# w076o.net
KiCad netlist of a schematic drawn in EAGLE
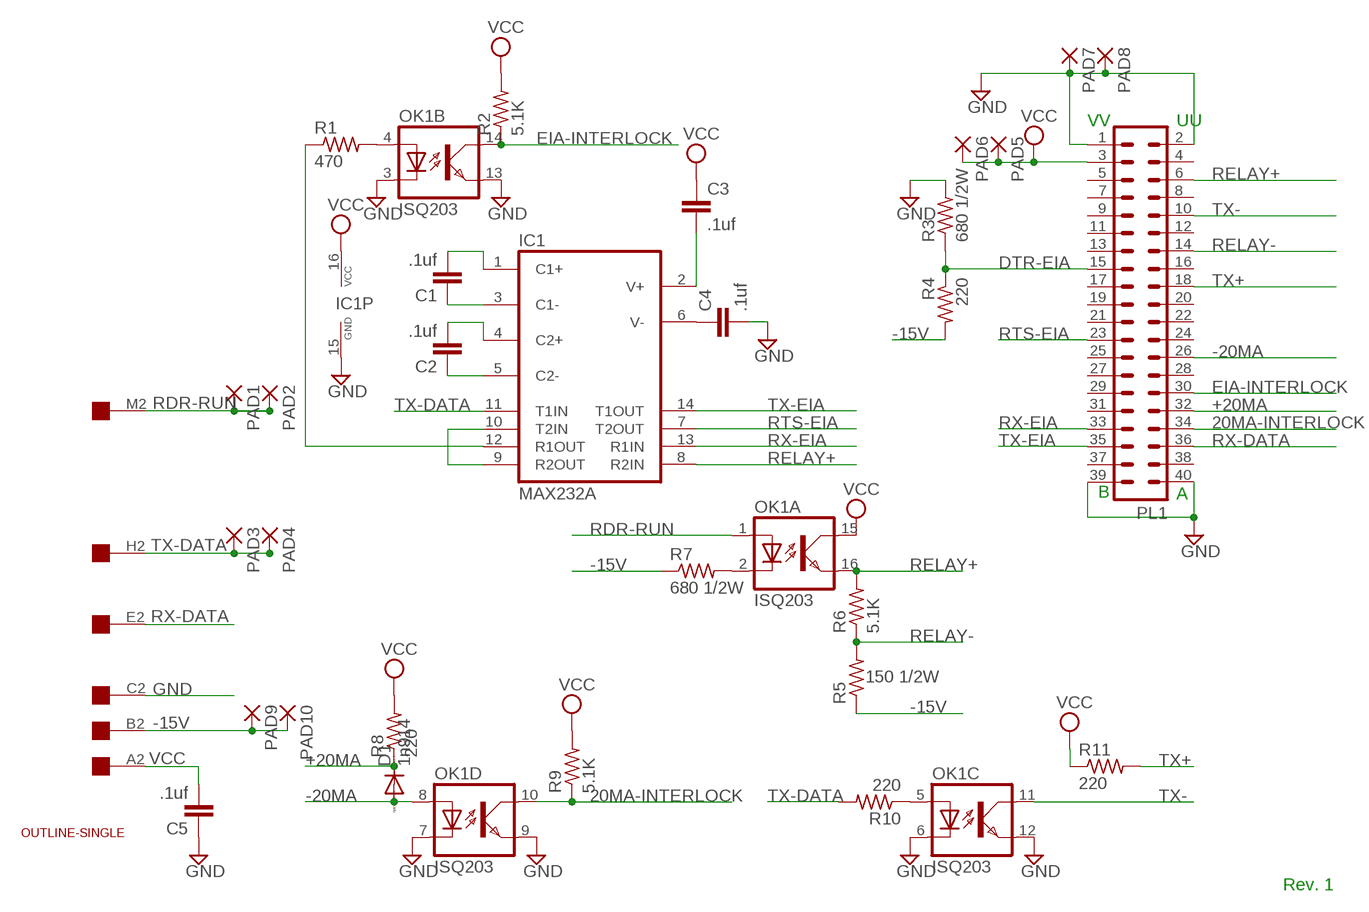
[diagram p0: schematic, sheet 1]

(export (version "E")
  (design (tool "Eeschema 10.0.6"))
  (components
    (comp (ref "C1")
      (value ".1uf")
      (footprint "eagle-import:C050-025X075")
      (libsource (lib "eagle-import") (part "C-EU050-025X075"))
    )
    (comp (ref "C2")
      (value ".1uf")
      (footprint "eagle-import:C050-025X075")
      (libsource (lib "eagle-import") (part "C-EU050-025X075"))
    )
    (comp (ref "C3")
      (value ".1uf")
      (footprint "eagle-import:C050-025X075")
      (libsource (lib "eagle-import") (part "C-EU050-025X075"))
    )
    (comp (ref "C4")
      (value ".1uf")
      (footprint "eagle-import:C050-025X075")
      (libsource (lib "eagle-import") (part "C-EU050-025X075"))
    )
    (comp (ref "C5")
      (value ".1uf")
      (footprint "eagle-import:C050-025X075")
      (libsource (lib "eagle-import") (part "C-EU050-025X075"))
    )
    (comp (ref "D1")
      (value "1n914")
      (footprint "eagle-import:DO41-10")
      (libsource (lib "eagle-import") (part "1N4004"))
    )
    (comp (ref "IC1")
      (value "MAX232A")
      (footprint "eagle-import:DIL16")
      (fields (field (name "MF") "MAXIM") (field (name "MPN") "MAX232ACPE+"))
      (libsource (lib "eagle-import") (part "MAX232"))
    )
    (comp (ref "OK1")
      (value "ISQ203")
      (footprint "eagle-import:DIL16")
      (fields (field (name "MF") "VISHAY/TELEFUNKEN") (field (name "MPN") "ILQ1"))
      (libsource (lib "eagle-import") (part "ILQ1"))
    )
    (comp (ref "PAD1")
      (value "1,6/0,8")
      (footprint "eagle-import:1,6_0,8")
      (libsource (lib "eagle-import") (part "1,6/0,8"))
    )
    (comp (ref "PAD2")
      (value "1,6/0,8")
      (footprint "eagle-import:1,6_0,8")
      (libsource (lib "eagle-import") (part "1,6/0,8"))
    )
    (comp (ref "PAD3")
      (value "1,6/0,8")
      (footprint "eagle-import:1,6_0,8")
      (libsource (lib "eagle-import") (part "1,6/0,8"))
    )
    (comp (ref "PAD4")
      (value "1,6/0,8")
      (footprint "eagle-import:1,6_0,8")
      (libsource (lib "eagle-import") (part "1,6/0,8"))
    )
    (comp (ref "PAD5")
      (value "1,6/0,8")
      (footprint "eagle-import:1,6_0,8")
      (libsource (lib "eagle-import") (part "1,6/0,8"))
    )
    (comp (ref "PAD6")
      (value "1,6/0,8")
      (footprint "eagle-import:1,6_0,8")
      (libsource (lib "eagle-import") (part "1,6/0,8"))
    )
    (comp (ref "PAD7")
      (value "1,6/0,8")
      (footprint "eagle-import:1,6_0,8")
      (libsource (lib "eagle-import") (part "1,6/0,8"))
    )
    (comp (ref "PAD8")
      (value "1,6/0,8")
      (footprint "eagle-import:1,6_0,8")
      (libsource (lib "eagle-import") (part "1,6/0,8"))
    )
    (comp (ref "PAD9")
      (value "1,6/0,8")
      (footprint "eagle-import:1,6_0,8")
      (libsource (lib "eagle-import") (part "1,6/0,8"))
    )
    (comp (ref "PAD10")
      (value "1,6/0,8")
      (footprint "eagle-import:1,6_0,8")
      (libsource (lib "eagle-import") (part "1,6/0,8"))
    )
    (comp (ref "PL1")
      (value "40H")
      (footprint "eagle-import:40H")
      (libsource (lib "eagle-import") (part "40H"))
    )
    (comp (ref "R1")
      (value "470")
      (footprint "eagle-import:0207_10")
      (libsource (lib "eagle-import") (part "R-US_0207/10"))
    )
    (comp (ref "R2")
      (value "5.1K")
      (footprint "eagle-import:0207_10")
      (libsource (lib "eagle-import") (part "R-US_0207/10"))
    )
    (comp (ref "R3")
      (value "680 1/2W")
      (footprint "eagle-import:0207_12")
      (libsource (lib "eagle-import") (part "R-US_0207/12"))
    )
    (comp (ref "R4")
      (value "220")
      (footprint "eagle-import:0207_10")
      (libsource (lib "eagle-import") (part "R-US_0207/10"))
    )
    (comp (ref "R5")
      (value "150 1/2W")
      (footprint "eagle-import:0207_12")
      (libsource (lib "eagle-import") (part "R-US_0207/12"))
    )
    (comp (ref "R6")
      (value "5.1K")
      (footprint "eagle-import:0207_10")
      (libsource (lib "eagle-import") (part "R-US_0207/10"))
    )
    (comp (ref "R7")
      (value "680 1/2W")
      (footprint "eagle-import:0207_12")
      (libsource (lib "eagle-import") (part "R-US_0207/12"))
    )
    (comp (ref "R8")
      (value "220")
      (footprint "eagle-import:0207_10")
      (libsource (lib "eagle-import") (part "R-US_0207/10"))
    )
    (comp (ref "R9")
      (value "5.1K")
      (footprint "eagle-import:0207_10")
      (libsource (lib "eagle-import") (part "R-US_0207/10"))
    )
    (comp (ref "R10")
      (value "220")
      (footprint "eagle-import:0207_10")
      (libsource (lib "eagle-import") (part "R-US_0207/10"))
    )
    (comp (ref "R11")
      (value "220")
      (footprint "eagle-import:0207_10")
      (libsource (lib "eagle-import") (part "R-US_0207/10"))
    )
    (comp (ref "U$1")
      (value "EDGE-2CONNECTOR")
      (footprint "eagle-import:EDGE-CON2")
      (libsource (lib "eagle-import") (part "EDGE-2CONNECTOR"))
    )
    (comp (ref "U$2")
      (value "OUTLINE-SINGLE")
      (footprint "eagle-import:SINGLE")
      (libsource (lib "eagle-import") (part "OUTLINE-SINGLE"))
    )
  )
  (nets
    (net (code "1") (name "/+20MA") (class "Default")
      (node (ref "D1") (pin "C") (pinfunction "C_C") (pintype "passive"))
      (node (ref "PL1") (pin "32") (pinfunction "32_32") (pintype "passive"))
      (node (ref "R8") (pin "1") (pinfunction "1_1") (pintype "passive"))
    )
    (net (code "2") (name "/-15V") (class "Default")
      (node (ref "PAD10") (pin "1") (pinfunction "P_1") (pintype "passive"))
      (node (ref "PAD9") (pin "1") (pinfunction "P_1") (pintype "passive"))
      (node (ref "R4") (pin "2") (pinfunction "2_2") (pintype "passive"))
      (node (ref "R5") (pin "1") (pinfunction "1_1") (pintype "passive"))
      (node (ref "R7") (pin "1") (pinfunction "1_1") (pintype "passive"))
      (node (ref "U$1") (pin "B2") (pinfunction "1_B2") (pintype "bidirectional"))
    )
    (net (code "3") (name "/-20MA") (class "Default")
      (node (ref "D1") (pin "A") (pinfunction "A_A") (pintype "passive"))
      (node (ref "OK1") (pin "8") (pinfunction "A_8") (pintype "passive"))
      (node (ref "PL1") (pin "26") (pinfunction "26_26") (pintype "passive"))
    )
    (net (code "4") (name "/20MA-INTERLOCK") (class "Default")
      (node (ref "OK1") (pin "10") (pinfunction "COL_10") (pintype "passive"))
      (node (ref "PL1") (pin "34") (pinfunction "34_34") (pintype "passive"))
      (node (ref "R9") (pin "1") (pinfunction "1_1") (pintype "passive"))
    )
    (net (code "5") (name "/DTR-EIA") (class "Default")
      (node (ref "PL1") (pin "15") (pinfunction "15_15") (pintype "passive"))
      (node (ref "R3") (pin "1") (pinfunction "1_1") (pintype "passive"))
      (node (ref "R4") (pin "1") (pinfunction "1_1") (pintype "passive"))
    )
    (net (code "6") (name "/EIA-INTERLOCK") (class "Default")
      (node (ref "OK1") (pin "14") (pinfunction "COL_14") (pintype "passive"))
      (node (ref "PL1") (pin "30") (pinfunction "30_30") (pintype "passive"))
      (node (ref "R2") (pin "1") (pinfunction "1_1") (pintype "passive"))
    )
    (net (code "7") (name "/RDR-RUN") (class "Default")
      (node (ref "OK1") (pin "1") (pinfunction "A_1") (pintype "passive"))
      (node (ref "PAD1") (pin "1") (pinfunction "P_1") (pintype "passive"))
      (node (ref "PAD2") (pin "1") (pinfunction "P_1") (pintype "passive"))
      (node (ref "U$1") (pin "M2") (pinfunction "1_M2") (pintype "bidirectional"))
    )
    (net (code "8") (name "/RELAY+") (class "Default")
      (node (ref "IC1") (pin "8") (pinfunction "R2IN_8") (pintype "input"))
      (node (ref "OK1") (pin "16") (pinfunction "EMIT_16") (pintype "passive"))
      (node (ref "PL1") (pin "6") (pinfunction "6_6") (pintype "passive"))
      (node (ref "R6") (pin "2") (pinfunction "2_2") (pintype "passive"))
    )
    (net (code "9") (name "/RELAY-") (class "Default")
      (node (ref "PL1") (pin "14") (pinfunction "14_14") (pintype "passive"))
      (node (ref "R5") (pin "2") (pinfunction "2_2") (pintype "passive"))
      (node (ref "R6") (pin "1") (pinfunction "1_1") (pintype "passive"))
    )
    (net (code "10") (name "/RTS-EIA") (class "Default")
      (node (ref "IC1") (pin "7") (pinfunction "T2OUT_7") (pintype "output"))
      (node (ref "PL1") (pin "23") (pinfunction "23_23") (pintype "passive"))
    )
    (net (code "11") (name "/RX-DATA") (class "Default")
      (node (ref "PL1") (pin "36") (pinfunction "36_36") (pintype "passive"))
      (node (ref "U$1") (pin "E2") (pinfunction "1_E2") (pintype "bidirectional"))
    )
    (net (code "12") (name "/RX-EIA") (class "Default")
      (node (ref "IC1") (pin "13") (pinfunction "R1IN_13") (pintype "input"))
      (node (ref "PL1") (pin "33") (pinfunction "33_33") (pintype "passive"))
    )
    (net (code "13") (name "/TX+") (class "Default")
      (node (ref "PL1") (pin "18") (pinfunction "18_18") (pintype "passive"))
      (node (ref "R11") (pin "2") (pinfunction "2_2") (pintype "passive"))
    )
    (net (code "14") (name "/TX-") (class "Default")
      (node (ref "OK1") (pin "11") (pinfunction "COL_11") (pintype "passive"))
      (node (ref "PL1") (pin "10") (pinfunction "10_10") (pintype "passive"))
    )
    (net (code "15") (name "/TX-DATA") (class "Default")
      (node (ref "IC1") (pin "11") (pinfunction "T1IN_11") (pintype "input"))
      (node (ref "PAD3") (pin "1") (pinfunction "P_1") (pintype "passive"))
      (node (ref "PAD4") (pin "1") (pinfunction "P_1") (pintype "passive"))
      (node (ref "R10") (pin "2") (pinfunction "2_2") (pintype "passive"))
      (node (ref "U$1") (pin "H2") (pinfunction "1_H2") (pintype "bidirectional"))
    )
    (net (code "16") (name "/TX-EIA") (class "Default")
      (node (ref "IC1") (pin "14") (pinfunction "T1OUT_14") (pintype "output"))
      (node (ref "PL1") (pin "35") (pinfunction "35_35") (pintype "passive"))
    )
    (net (code "17") (name "GND") (class "Default")
      (node (ref "C4") (pin "2") (pinfunction "2_2") (pintype "passive"))
      (node (ref "C5") (pin "1") (pinfunction "1_1") (pintype "passive"))
      (node (ref "IC1") (pin "15") (pinfunction "GND_15") (pintype "power_in"))
      (node (ref "OK1") (pin "12") (pinfunction "EMIT_12") (pintype "passive"))
      (node (ref "OK1") (pin "13") (pinfunction "EMIT_13") (pintype "passive"))
      (node (ref "OK1") (pin "3") (pinfunction "C_3") (pintype "passive"))
      (node (ref "OK1") (pin "6") (pinfunction "C_6") (pintype "passive"))
      (node (ref "OK1") (pin "7") (pinfunction "C_7") (pintype "passive"))
      (node (ref "OK1") (pin "9") (pinfunction "EMIT_9") (pintype "passive"))
      (node (ref "PAD7") (pin "1") (pinfunction "P_1") (pintype "passive"))
      (node (ref "PAD8") (pin "1") (pinfunction "P_1") (pintype "passive"))
      (node (ref "PL1") (pin "1") (pinfunction "1_1") (pintype "passive"))
      (node (ref "PL1") (pin "2") (pinfunction "2_2") (pintype "passive"))
      (node (ref "PL1") (pin "39") (pinfunction "39_39") (pintype "passive"))
      (node (ref "PL1") (pin "40") (pinfunction "40_40") (pintype "passive"))
      (node (ref "R3") (pin "2") (pinfunction "2_2") (pintype "passive"))
      (node (ref "U$1") (pin "C2") (pinfunction "1_C2") (pintype "bidirectional"))
    )
    (net (code "18") (name "Net-(IC1A-C1+)") (class "Default")
      (node (ref "C1") (pin "2") (pinfunction "2_2") (pintype "passive"))
      (node (ref "IC1") (pin "1") (pinfunction "C1+_1") (pintype "bidirectional"))
    )
    (net (code "19") (name "Net-(IC1A-C1-)") (class "Default")
      (node (ref "C1") (pin "1") (pinfunction "1_1") (pintype "passive"))
      (node (ref "IC1") (pin "3") (pinfunction "C1-_3") (pintype "bidirectional"))
    )
    (net (code "20") (name "Net-(IC1A-C2+)") (class "Default")
      (node (ref "C2") (pin "2") (pinfunction "2_2") (pintype "passive"))
      (node (ref "IC1") (pin "4") (pinfunction "C2+_4") (pintype "bidirectional"))
    )
    (net (code "21") (name "Net-(IC1A-C2-)") (class "Default")
      (node (ref "C2") (pin "1") (pinfunction "1_1") (pintype "passive"))
      (node (ref "IC1") (pin "5") (pinfunction "C2-_5") (pintype "bidirectional"))
    )
    (net (code "22") (name "Net-(IC1A-R1OUT)") (class "Default")
      (node (ref "IC1") (pin "12") (pinfunction "R1OUT_12") (pintype "output"))
      (node (ref "R1") (pin "1") (pinfunction "1_1") (pintype "passive"))
    )
    (net (code "23") (name "Net-(IC1A-R2OUT)") (class "Default")
      (node (ref "IC1") (pin "10") (pinfunction "T2IN_10") (pintype "input"))
      (node (ref "IC1") (pin "9") (pinfunction "R2OUT_9") (pintype "output"))
    )
    (net (code "24") (name "Net-(IC1A-V+)") (class "Default")
      (node (ref "C3") (pin "2") (pinfunction "2_2") (pintype "passive"))
      (node (ref "IC1") (pin "2") (pinfunction "V+_2") (pintype "bidirectional"))
    )
    (net (code "25") (name "Net-(IC1A-V-)") (class "Default")
      (node (ref "C4") (pin "1") (pinfunction "1_1") (pintype "passive"))
      (node (ref "IC1") (pin "6") (pinfunction "V-_6") (pintype "bidirectional"))
    )
    (net (code "26") (name "Net-(OK1A-C)") (class "Default")
      (node (ref "OK1") (pin "2") (pinfunction "C_2") (pintype "passive"))
      (node (ref "R7") (pin "2") (pinfunction "2_2") (pintype "passive"))
    )
    (net (code "27") (name "Net-(OK1B-A)") (class "Default")
      (node (ref "OK1") (pin "4") (pinfunction "A_4") (pintype "passive"))
      (node (ref "R1") (pin "2") (pinfunction "2_2") (pintype "passive"))
    )
    (net (code "28") (name "Net-(OK1C-A)") (class "Default")
      (node (ref "OK1") (pin "5") (pinfunction "A_5") (pintype "passive"))
      (node (ref "R10") (pin "1") (pinfunction "1_1") (pintype "passive"))
    )
    (net (code "29") (name "VCC") (class "Default")
      (node (ref "C3") (pin "1") (pinfunction "1_1") (pintype "passive"))
      (node (ref "C5") (pin "2") (pinfunction "2_2") (pintype "passive"))
      (node (ref "IC1") (pin "16") (pinfunction "VCC_16") (pintype "power_in"))
      (node (ref "OK1") (pin "15") (pinfunction "COL_15") (pintype "passive"))
      (node (ref "PAD5") (pin "1") (pinfunction "P_1") (pintype "passive"))
      (node (ref "PAD6") (pin "1") (pinfunction "P_1") (pintype "passive"))
      (node (ref "PL1") (pin "3") (pinfunction "3_3") (pintype "passive"))
      (node (ref "R11") (pin "1") (pinfunction "1_1") (pintype "passive"))
      (node (ref "R2") (pin "2") (pinfunction "2_2") (pintype "passive"))
      (node (ref "R8") (pin "2") (pinfunction "2_2") (pintype "passive"))
      (node (ref "R9") (pin "2") (pinfunction "2_2") (pintype "passive"))
      (node (ref "U$1") (pin "A2") (pinfunction "1_A2") (pintype "bidirectional"))
    )
    (net (code "30") (name "unconnected-(PL1-Pad4)") (class "Default")
      (node (ref "PL1") (pin "4") (pinfunction "4_4") (pintype "passive"))
    )
    (net (code "31") (name "unconnected-(PL1-Pad5)") (class "Default")
      (node (ref "PL1") (pin "5") (pinfunction "5_5") (pintype "passive"))
    )
    (net (code "32") (name "unconnected-(PL1-Pad7)") (class "Default")
      (node (ref "PL1") (pin "7") (pinfunction "7_7") (pintype "passive"))
    )
    (net (code "33") (name "unconnected-(PL1-Pad8)") (class "Default")
      (node (ref "PL1") (pin "8") (pinfunction "8_8") (pintype "passive"))
    )
    (net (code "34") (name "unconnected-(PL1-Pad9)") (class "Default")
      (node (ref "PL1") (pin "9") (pinfunction "9_9") (pintype "passive"))
    )
    (net (code "35") (name "unconnected-(PL1-Pad11)") (class "Default")
      (node (ref "PL1") (pin "11") (pinfunction "11_11") (pintype "passive"))
    )
    (net (code "36") (name "unconnected-(PL1-Pad12)") (class "Default")
      (node (ref "PL1") (pin "12") (pinfunction "12_12") (pintype "passive"))
    )
    (net (code "37") (name "unconnected-(PL1-Pad13)") (class "Default")
      (node (ref "PL1") (pin "13") (pinfunction "13_13") (pintype "passive"))
    )
    (net (code "38") (name "unconnected-(PL1-Pad16)") (class "Default")
      (node (ref "PL1") (pin "16") (pinfunction "16_16") (pintype "passive"))
    )
    (net (code "39") (name "unconnected-(PL1-Pad17)") (class "Default")
      (node (ref "PL1") (pin "17") (pinfunction "17_17") (pintype "passive"))
    )
    (net (code "40") (name "unconnected-(PL1-Pad19)") (class "Default")
      (node (ref "PL1") (pin "19") (pinfunction "19_19") (pintype "passive"))
    )
    (net (code "41") (name "unconnected-(PL1-Pad20)") (class "Default")
      (node (ref "PL1") (pin "20") (pinfunction "20_20") (pintype "passive"))
    )
    (net (code "42") (name "unconnected-(PL1-Pad21)") (class "Default")
      (node (ref "PL1") (pin "21") (pinfunction "21_21") (pintype "passive"))
    )
    (net (code "43") (name "unconnected-(PL1-Pad22)") (class "Default")
      (node (ref "PL1") (pin "22") (pinfunction "22_22") (pintype "passive"))
    )
    (net (code "44") (name "unconnected-(PL1-Pad24)") (class "Default")
      (node (ref "PL1") (pin "24") (pinfunction "24_24") (pintype "passive"))
    )
    (net (code "45") (name "unconnected-(PL1-Pad25)") (class "Default")
      (node (ref "PL1") (pin "25") (pinfunction "25_25") (pintype "passive"))
    )
    (net (code "46") (name "unconnected-(PL1-Pad27)") (class "Default")
      (node (ref "PL1") (pin "27") (pinfunction "27_27") (pintype "passive"))
    )
    (net (code "47") (name "unconnected-(PL1-Pad28)") (class "Default")
      (node (ref "PL1") (pin "28") (pinfunction "28_28") (pintype "passive"))
    )
    (net (code "48") (name "unconnected-(PL1-Pad29)") (class "Default")
      (node (ref "PL1") (pin "29") (pinfunction "29_29") (pintype "passive"))
    )
    (net (code "49") (name "unconnected-(PL1-Pad31)") (class "Default")
      (node (ref "PL1") (pin "31") (pinfunction "31_31") (pintype "passive"))
    )
    (net (code "50") (name "unconnected-(PL1-Pad37)") (class "Default")
      (node (ref "PL1") (pin "37") (pinfunction "37_37") (pintype "passive"))
    )
    (net (code "51") (name "unconnected-(PL1-Pad38)") (class "Default")
      (node (ref "PL1") (pin "38") (pinfunction "38_38") (pintype "passive"))
    )
  )
)
